# BlnTest.net
KiCad netlist of a schematic drawn in Altium Designer
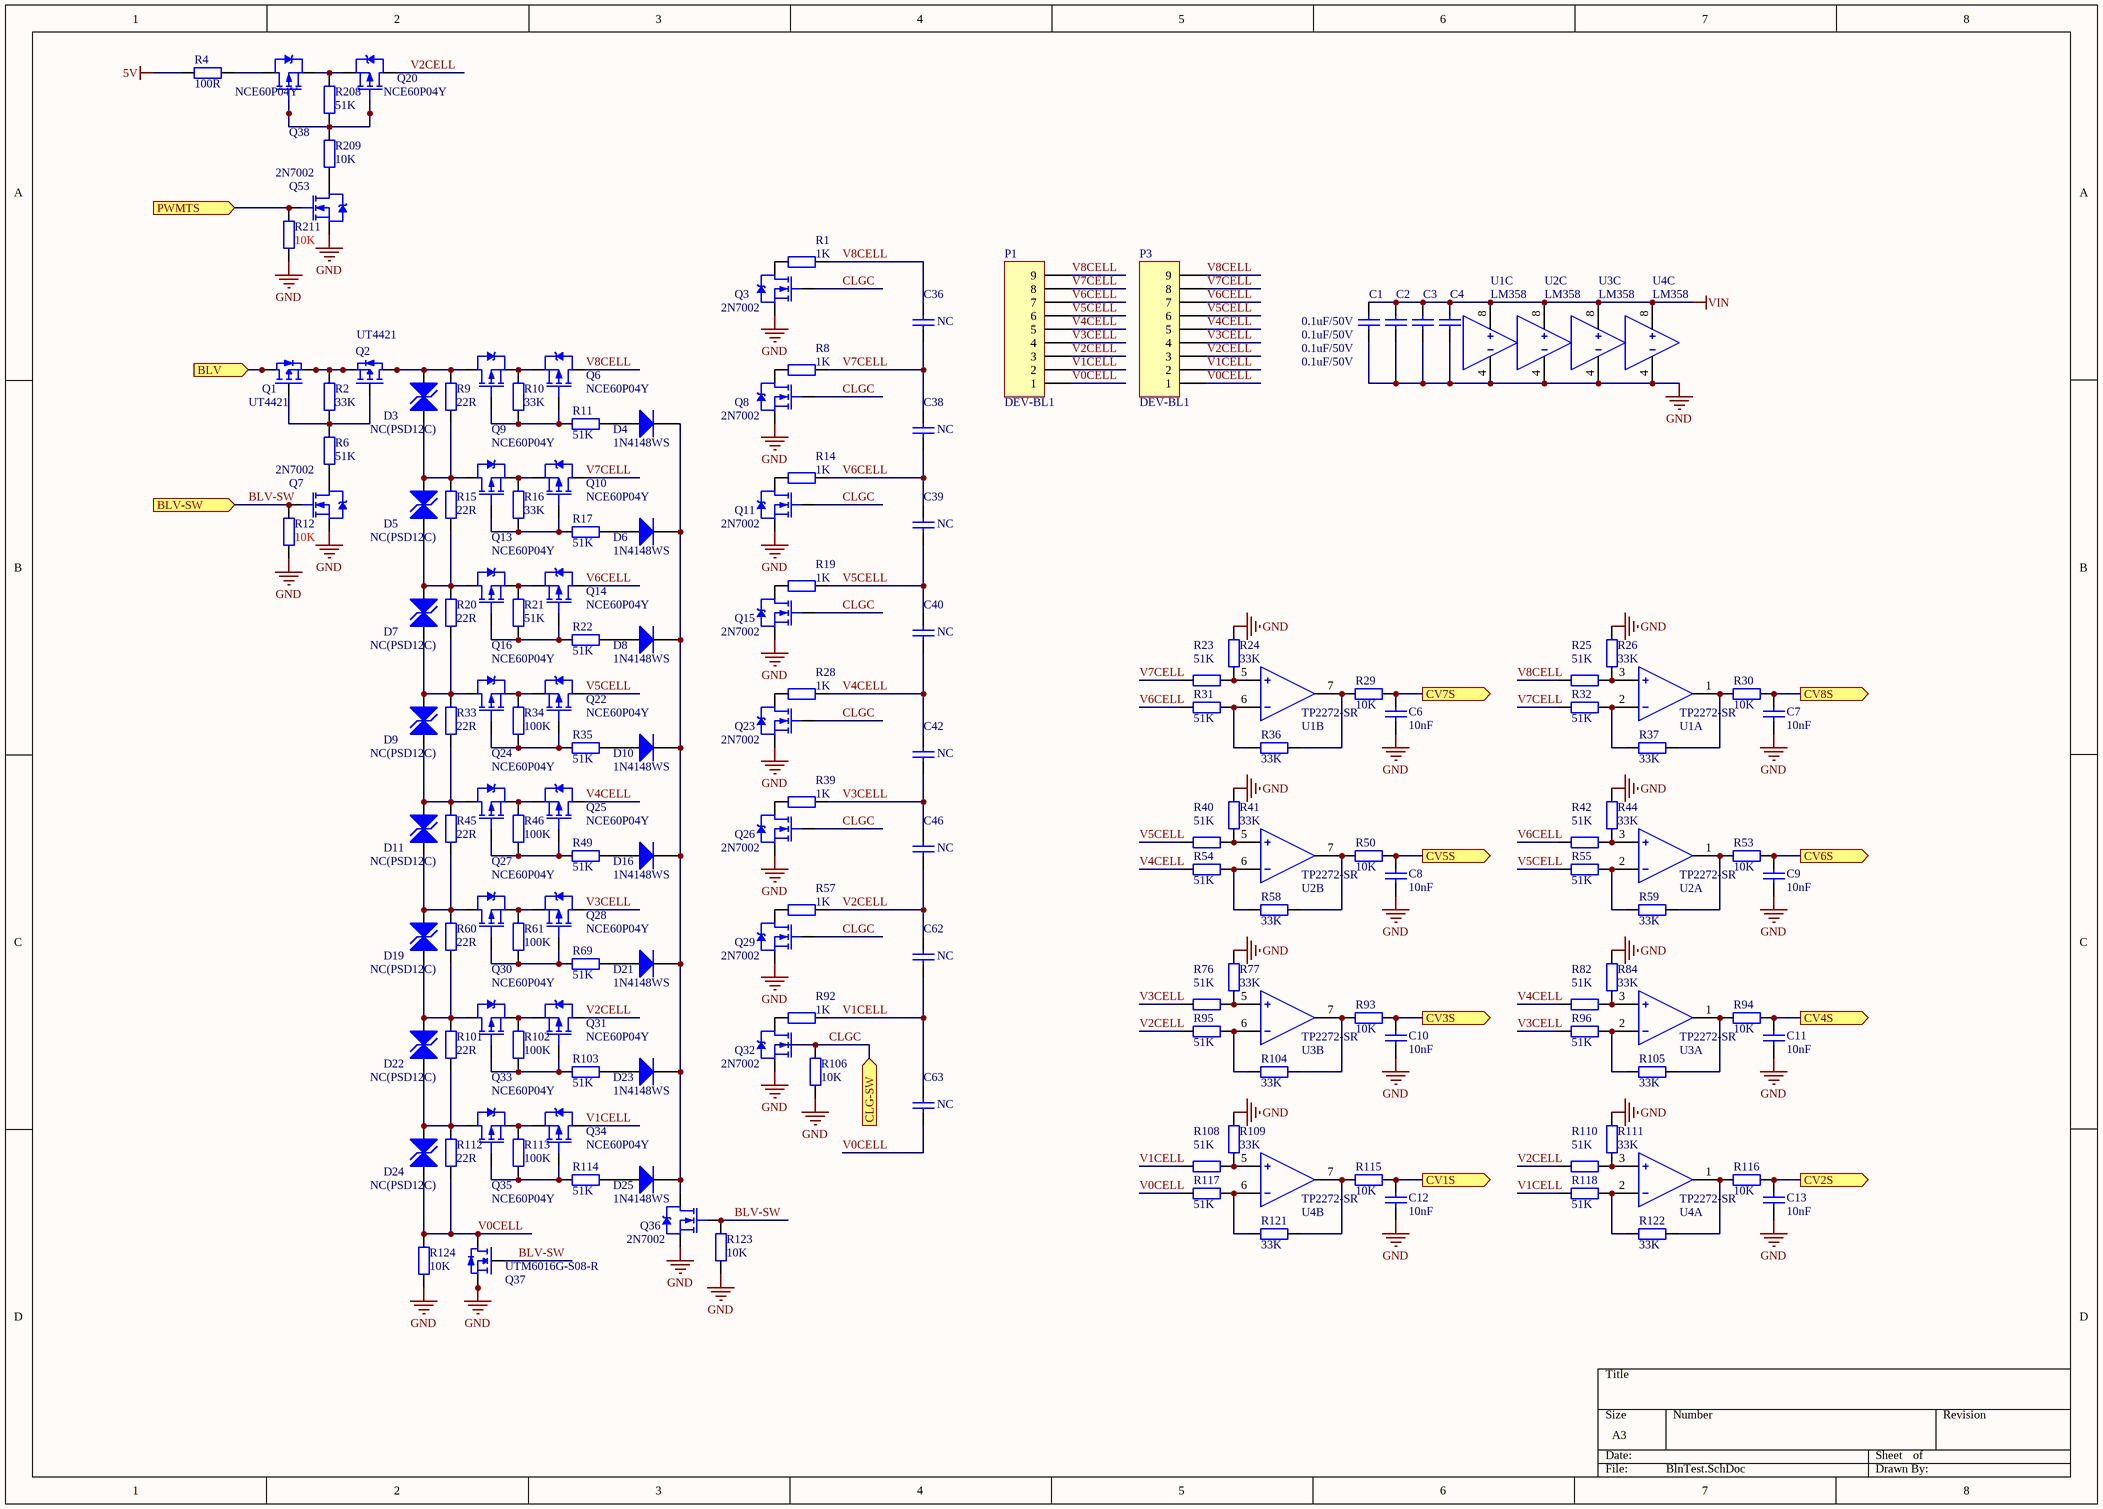
[diagram p0: BlnTest.SchDoc]

(export (version "E")
  (design (tool "Eeschema 10.0.6"))
  (components
    (comp (ref "C1")
      (value "0.1uF/50V")
      (footprint "C-0603")
      (description "Capacitor")
      (fields (field (name "PUBLISHER") "Altium Limited"))
      (libsource (lib "Miscellaneous Devices") (part "Cap"))
    )
    (comp (ref "C2")
      (value "0.1uF/50V")
      (footprint "C-0603")
      (description "Capacitor")
      (fields (field (name "PUBLISHER") "Altium Limited"))
      (libsource (lib "Miscellaneous Devices") (part "Cap"))
    )
    (comp (ref "C3")
      (value "0.1uF/50V")
      (footprint "C-0603")
      (description "Capacitor")
      (fields (field (name "PUBLISHER") "Altium Limited"))
      (libsource (lib "Miscellaneous Devices") (part "Cap"))
    )
    (comp (ref "C4")
      (value "0.1uF/50V")
      (footprint "C-0603")
      (description "Capacitor")
      (fields (field (name "PUBLISHER") "Altium Limited"))
      (libsource (lib "Miscellaneous Devices") (part "Cap"))
    )
    (comp (ref "C6")
      (value "10nF")
      (footprint "C-0603")
      (description "Capacitor")
      (fields (field (name "PUBLISHER") "Altium Limited"))
      (libsource (lib "Miscellaneous Devices") (part "Cap"))
    )
    (comp (ref "C7")
      (value "10nF")
      (footprint "C-0603")
      (description "Capacitor")
      (fields (field (name "PUBLISHER") "Altium Limited"))
      (libsource (lib "Miscellaneous Devices") (part "Cap"))
    )
    (comp (ref "C8")
      (value "10nF")
      (footprint "C-0603")
      (description "Capacitor")
      (fields (field (name "PUBLISHER") "Altium Limited"))
      (libsource (lib "Miscellaneous Devices") (part "Cap"))
    )
    (comp (ref "C9")
      (value "10nF")
      (footprint "C-0603")
      (description "Capacitor")
      (fields (field (name "PUBLISHER") "Altium Limited"))
      (libsource (lib "Miscellaneous Devices") (part "Cap"))
    )
    (comp (ref "C10")
      (value "10nF")
      (footprint "C-0603")
      (description "Capacitor")
      (fields (field (name "PUBLISHER") "Altium Limited"))
      (libsource (lib "Miscellaneous Devices") (part "Cap"))
    )
    (comp (ref "C11")
      (value "10nF")
      (footprint "C-0603")
      (description "Capacitor")
      (fields (field (name "PUBLISHER") "Altium Limited"))
      (libsource (lib "Miscellaneous Devices") (part "Cap"))
    )
    (comp (ref "C12")
      (value "10nF")
      (footprint "C-0603")
      (description "Capacitor")
      (fields (field (name "PUBLISHER") "Altium Limited"))
      (libsource (lib "Miscellaneous Devices") (part "Cap"))
    )
    (comp (ref "C13")
      (value "10nF")
      (footprint "C-0603")
      (description "Capacitor")
      (fields (field (name "PUBLISHER") "Altium Limited"))
      (libsource (lib "Miscellaneous Devices") (part "Cap"))
    )
    (comp (ref "C36")
      (value "NC")
      (footprint "C-0805")
      (description "Capacitor")
      (fields (field (name "PUBLISHER") "Altium Limited"))
      (libsource (lib "Miscellaneous Devices") (part "Cap"))
    )
    (comp (ref "C38")
      (value "NC")
      (footprint "C-0805")
      (description "Capacitor")
      (fields (field (name "PUBLISHER") "Altium Limited"))
      (libsource (lib "Miscellaneous Devices") (part "Cap"))
    )
    (comp (ref "C39")
      (value "NC")
      (footprint "C-0805")
      (description "Capacitor")
      (fields (field (name "PUBLISHER") "Altium Limited"))
      (libsource (lib "Miscellaneous Devices") (part "Cap"))
    )
    (comp (ref "C40")
      (value "NC")
      (footprint "C-0805")
      (description "Capacitor")
      (fields (field (name "PUBLISHER") "Altium Limited"))
      (libsource (lib "Miscellaneous Devices") (part "Cap"))
    )
    (comp (ref "C42")
      (value "NC")
      (footprint "C-0805")
      (description "Capacitor")
      (fields (field (name "PUBLISHER") "Altium Limited"))
      (libsource (lib "Miscellaneous Devices") (part "Cap"))
    )
    (comp (ref "C46")
      (value "NC")
      (footprint "C-0805")
      (description "Capacitor")
      (fields (field (name "PUBLISHER") "Altium Limited"))
      (libsource (lib "Miscellaneous Devices") (part "Cap"))
    )
    (comp (ref "C62")
      (value "NC")
      (footprint "C-0805")
      (description "Capacitor")
      (fields (field (name "PUBLISHER") "Altium Limited"))
      (libsource (lib "Miscellaneous Devices") (part "Cap"))
    )
    (comp (ref "C63")
      (value "NC")
      (footprint "C-0805")
      (description "Capacitor")
      (fields (field (name "PUBLISHER") "Altium Limited"))
      (libsource (lib "Miscellaneous Devices") (part "Cap"))
    )
    (comp (ref "D3") (value "NC(PSD12C)") (footprint "SOD-323") (libsource (lib "ToboxStd") (part "TVS-D")))
    (comp (ref "D4")
      (value "1N4148WS")
      (footprint "SOD-323")
      (description "Default Diode")
      (fields (field (name "PUBLISHER") "Altium Limited"))
      (libsource (lib "Miscellaneous Devices") (part "Diode"))
    )
    (comp (ref "D5") (value "NC(PSD12C)") (footprint "SOD-323") (libsource (lib "ToboxStd") (part "TVS-D")))
    (comp (ref "D6")
      (value "1N4148WS")
      (footprint "SOD-323")
      (description "Default Diode")
      (fields (field (name "PUBLISHER") "Altium Limited"))
      (libsource (lib "Miscellaneous Devices") (part "Diode"))
    )
    (comp (ref "D7") (value "NC(PSD12C)") (footprint "SOD-323") (libsource (lib "ToboxStd") (part "TVS-D")))
    (comp (ref "D8")
      (value "1N4148WS")
      (footprint "SOD-323")
      (description "Default Diode")
      (fields (field (name "PUBLISHER") "Altium Limited"))
      (libsource (lib "Miscellaneous Devices") (part "Diode"))
    )
    (comp (ref "D9") (value "NC(PSD12C)") (footprint "SOD-323") (libsource (lib "ToboxStd") (part "TVS-D")))
    (comp (ref "D10")
      (value "1N4148WS")
      (footprint "SOD-323")
      (description "Default Diode")
      (fields (field (name "PUBLISHER") "Altium Limited"))
      (libsource (lib "Miscellaneous Devices") (part "Diode"))
    )
    (comp (ref "D11") (value "NC(PSD12C)") (footprint "SOD-323") (libsource (lib "ToboxStd") (part "TVS-D")))
    (comp (ref "D16")
      (value "1N4148WS")
      (footprint "SOD-323")
      (description "Default Diode")
      (fields (field (name "PUBLISHER") "Altium Limited"))
      (libsource (lib "Miscellaneous Devices") (part "Diode"))
    )
    (comp (ref "D19") (value "NC(PSD12C)") (footprint "SOD-323") (libsource (lib "ToboxStd") (part "TVS-D")))
    (comp (ref "D21")
      (value "1N4148WS")
      (footprint "SOD-323")
      (description "Default Diode")
      (fields (field (name "PUBLISHER") "Altium Limited"))
      (libsource (lib "Miscellaneous Devices") (part "Diode"))
    )
    (comp (ref "D22") (value "NC(PSD12C)") (footprint "SOD-323") (libsource (lib "ToboxStd") (part "TVS-D")))
    (comp (ref "D23")
      (value "1N4148WS")
      (footprint "SOD-323")
      (description "Default Diode")
      (fields (field (name "PUBLISHER") "Altium Limited"))
      (libsource (lib "Miscellaneous Devices") (part "Diode"))
    )
    (comp (ref "D24") (value "NC(PSD12C)") (footprint "SOD-323") (libsource (lib "ToboxStd") (part "TVS-D")))
    (comp (ref "D25")
      (value "1N4148WS")
      (footprint "SOD-323")
      (description "Default Diode")
      (fields (field (name "PUBLISHER") "Altium Limited"))
      (libsource (lib "Miscellaneous Devices") (part "Diode"))
    )
    (comp (ref "P1")
      (value "DEV-BL1")
      (footprint "XH 2.54-9P")
      (description "Header, 9-Pin")
      (fields (field (name "PUBLISHER") "Altium Limited"))
      (libsource (lib "Miscellaneous Connectors") (part "Header 9"))
    )
    (comp (ref "P3")
      (value "DEV-BL1")
      (footprint "XH 2.54-9P")
      (description "Header, 9-Pin")
      (fields (field (name "PUBLISHER") "Altium Limited"))
      (libsource (lib "Miscellaneous Connectors") (part "Header 9"))
    )
    (comp (ref "Q1")
      (value "UT4421")
      (footprint "SOIC8")
      (description "SO8-PMOS")
      (libsource (lib "Tobox") (part "SO8-PMOS"))
    )
    (comp (ref "Q2")
      (value "UT4421")
      (footprint "SOIC8")
      (description "SO8-PMOS")
      (libsource (lib "Tobox") (part "SO8-PMOS"))
    )
    (comp (ref "Q3")
      (value "2N7002")
      (footprint "SOT23-3")
      (description "N-Channel Power MOSFET")
      (fields (field (name "PUBLISHER") "Altium Limited"))
      (libsource (lib "Miscellaneous Devices") (part "NMOS-2"))
    )
    (comp (ref "Q6")
      (value "NCE60P04Y")
      (footprint "SOT23-3")
      (description "P-Channel Power MOSFET")
      (fields (field (name "PUBLISHER") "Altium Limited"))
      (libsource (lib "Miscellaneous Devices") (part "PMOS-2"))
    )
    (comp (ref "Q7")
      (value "2N7002")
      (footprint "SOT23-3")
      (description "N-Channel Power MOSFET")
      (fields (field (name "PUBLISHER") "Altium Limited"))
      (libsource (lib "Miscellaneous Devices") (part "NMOS-2"))
    )
    (comp (ref "Q8")
      (value "2N7002")
      (footprint "SOT23-3")
      (description "N-Channel Power MOSFET")
      (fields (field (name "PUBLISHER") "Altium Limited"))
      (libsource (lib "Miscellaneous Devices") (part "NMOS-2"))
    )
    (comp (ref "Q9")
      (value "NCE60P04Y")
      (footprint "SOT23-3")
      (description "P-Channel Power MOSFET")
      (fields (field (name "PUBLISHER") "Altium Limited"))
      (libsource (lib "Miscellaneous Devices") (part "PMOS-2"))
    )
    (comp (ref "Q10")
      (value "NCE60P04Y")
      (footprint "SOT23-3")
      (description "P-Channel Power MOSFET")
      (fields (field (name "PUBLISHER") "Altium Limited"))
      (libsource (lib "Miscellaneous Devices") (part "PMOS-2"))
    )
    (comp (ref "Q11")
      (value "2N7002")
      (footprint "SOT23-3")
      (description "N-Channel Power MOSFET")
      (fields (field (name "PUBLISHER") "Altium Limited"))
      (libsource (lib "Miscellaneous Devices") (part "NMOS-2"))
    )
    (comp (ref "Q13")
      (value "NCE60P04Y")
      (footprint "SOT23-3")
      (description "P-Channel Power MOSFET")
      (fields (field (name "PUBLISHER") "Altium Limited"))
      (libsource (lib "Miscellaneous Devices") (part "PMOS-2"))
    )
    (comp (ref "Q14")
      (value "NCE60P04Y")
      (footprint "SOT23-3")
      (description "P-Channel Power MOSFET")
      (fields (field (name "PUBLISHER") "Altium Limited"))
      (libsource (lib "Miscellaneous Devices") (part "PMOS-2"))
    )
    (comp (ref "Q15")
      (value "2N7002")
      (footprint "SOT23-3")
      (description "N-Channel Power MOSFET")
      (fields (field (name "PUBLISHER") "Altium Limited"))
      (libsource (lib "Miscellaneous Devices") (part "NMOS-2"))
    )
    (comp (ref "Q16")
      (value "NCE60P04Y")
      (footprint "SOT23-3")
      (description "P-Channel Power MOSFET")
      (fields (field (name "PUBLISHER") "Altium Limited"))
      (libsource (lib "Miscellaneous Devices") (part "PMOS-2"))
    )
    (comp (ref "Q20")
      (value "NCE60P04Y")
      (footprint "SOT23-3")
      (description "P-Channel Power MOSFET")
      (fields (field (name "PUBLISHER") "Altium Limited"))
      (libsource (lib "Miscellaneous Devices") (part "PMOS-2"))
    )
    (comp (ref "Q22")
      (value "NCE60P04Y")
      (footprint "SOT23-3")
      (description "P-Channel Power MOSFET")
      (fields (field (name "PUBLISHER") "Altium Limited"))
      (libsource (lib "Miscellaneous Devices") (part "PMOS-2"))
    )
    (comp (ref "Q23")
      (value "2N7002")
      (footprint "SOT23-3")
      (description "N-Channel Power MOSFET")
      (fields (field (name "PUBLISHER") "Altium Limited"))
      (libsource (lib "Miscellaneous Devices") (part "NMOS-2"))
    )
    (comp (ref "Q24")
      (value "NCE60P04Y")
      (footprint "SOT23-3")
      (description "P-Channel Power MOSFET")
      (fields (field (name "PUBLISHER") "Altium Limited"))
      (libsource (lib "Miscellaneous Devices") (part "PMOS-2"))
    )
    (comp (ref "Q25")
      (value "NCE60P04Y")
      (footprint "SOT23-3")
      (description "P-Channel Power MOSFET")
      (fields (field (name "PUBLISHER") "Altium Limited"))
      (libsource (lib "Miscellaneous Devices") (part "PMOS-2"))
    )
    (comp (ref "Q26")
      (value "2N7002")
      (footprint "SOT23-3")
      (description "N-Channel Power MOSFET")
      (fields (field (name "PUBLISHER") "Altium Limited"))
      (libsource (lib "Miscellaneous Devices") (part "NMOS-2"))
    )
    (comp (ref "Q27")
      (value "NCE60P04Y")
      (footprint "SOT23-3")
      (description "P-Channel Power MOSFET")
      (fields (field (name "PUBLISHER") "Altium Limited"))
      (libsource (lib "Miscellaneous Devices") (part "PMOS-2"))
    )
    (comp (ref "Q28")
      (value "NCE60P04Y")
      (footprint "SOT23-3")
      (description "P-Channel Power MOSFET")
      (fields (field (name "PUBLISHER") "Altium Limited"))
      (libsource (lib "Miscellaneous Devices") (part "PMOS-2"))
    )
    (comp (ref "Q29")
      (value "2N7002")
      (footprint "SOT23-3")
      (description "N-Channel Power MOSFET")
      (fields (field (name "PUBLISHER") "Altium Limited"))
      (libsource (lib "Miscellaneous Devices") (part "NMOS-2"))
    )
    (comp (ref "Q30")
      (value "NCE60P04Y")
      (footprint "SOT23-3")
      (description "P-Channel Power MOSFET")
      (fields (field (name "PUBLISHER") "Altium Limited"))
      (libsource (lib "Miscellaneous Devices") (part "PMOS-2"))
    )
    (comp (ref "Q31")
      (value "NCE60P04Y")
      (footprint "SOT23-3")
      (description "P-Channel Power MOSFET")
      (fields (field (name "PUBLISHER") "Altium Limited"))
      (libsource (lib "Miscellaneous Devices") (part "PMOS-2"))
    )
    (comp (ref "Q32")
      (value "2N7002")
      (footprint "SOT23-3")
      (description "N-Channel Power MOSFET")
      (fields (field (name "PUBLISHER") "Altium Limited"))
      (libsource (lib "Miscellaneous Devices") (part "NMOS-2"))
    )
    (comp (ref "Q33")
      (value "NCE60P04Y")
      (footprint "SOT23-3")
      (description "P-Channel Power MOSFET")
      (fields (field (name "PUBLISHER") "Altium Limited"))
      (libsource (lib "Miscellaneous Devices") (part "PMOS-2"))
    )
    (comp (ref "Q34")
      (value "NCE60P04Y")
      (footprint "SOT23-3")
      (description "P-Channel Power MOSFET")
      (fields (field (name "PUBLISHER") "Altium Limited"))
      (libsource (lib "Miscellaneous Devices") (part "PMOS-2"))
    )
    (comp (ref "Q35")
      (value "NCE60P04Y")
      (footprint "SOT23-3")
      (description "P-Channel Power MOSFET")
      (fields (field (name "PUBLISHER") "Altium Limited"))
      (libsource (lib "Miscellaneous Devices") (part "PMOS-2"))
    )
    (comp (ref "Q36")
      (value "2N7002")
      (footprint "SOT23-3")
      (description "N-Channel Power MOSFET")
      (fields (field (name "PUBLISHER") "Altium Limited"))
      (libsource (lib "Miscellaneous Devices") (part "NMOS-2"))
    )
    (comp (ref "Q37")
      (value "UTM6016G-S08-R")
      (footprint "SOIC8")
      (description "SO8-NMOS")
      (libsource (lib "Tobox") (part "SO8-NMOS"))
    )
    (comp (ref "Q38")
      (value "NCE60P04Y")
      (footprint "SOT23-3")
      (description "P-Channel Power MOSFET")
      (fields (field (name "PUBLISHER") "Altium Limited"))
      (libsource (lib "Miscellaneous Devices") (part "PMOS-2"))
    )
    (comp (ref "Q53")
      (value "2N7002")
      (footprint "SOT23-3")
      (description "N-Channel Power MOSFET")
      (fields (field (name "PUBLISHER") "Altium Limited"))
      (libsource (lib "Miscellaneous Devices") (part "NMOS-2"))
    )
    (comp (ref "R1")
      (value "1K")
      (footprint "R-0603")
      (description "Resistor")
      (fields (field (name "PUBLISHER") "Altium Limited"))
      (libsource (lib "") (part "Res2_2"))
    )
    (comp (ref "R2")
      (value "33K")
      (footprint "R-0603")
      (description "Resistor")
      (fields (field (name "PUBLISHER") "Altium Limited"))
      (libsource (lib "") (part "Res2_2"))
    )
    (comp (ref "R4")
      (value "100R")
      (footprint "R-0603")
      (description "Resistor")
      (fields (field (name "PUBLISHER") "Altium Limited"))
      (libsource (lib "") (part "Res2_3"))
    )
    (comp (ref "R6")
      (value "51K")
      (footprint "R-0603")
      (description "Resistor")
      (fields (field (name "PUBLISHER") "Altium Limited"))
      (libsource (lib "") (part "Res2_2"))
    )
    (comp (ref "R8")
      (value "1K")
      (footprint "R-0603")
      (description "Resistor")
      (fields (field (name "PUBLISHER") "Altium Limited"))
      (libsource (lib "") (part "Res2_2"))
    )
    (comp (ref "R9")
      (value "22R")
      (footprint "RES 3W-S")
      (description "Resistor")
      (fields (field (name "PUBLISHER") "Altium Limited"))
      (libsource (lib "") (part "Res2_1"))
    )
    (comp (ref "R10")
      (value "33K")
      (footprint "R-0603")
      (description "Resistor")
      (fields (field (name "PUBLISHER") "Altium Limited"))
      (libsource (lib "") (part "Res2_3"))
    )
    (comp (ref "R11")
      (value "51K")
      (footprint "R-0603")
      (description "Resistor")
      (fields (field (name "PUBLISHER") "Altium Limited"))
      (libsource (lib "Miscellaneous Devices") (part "Res2"))
    )
    (comp (ref "R12")
      (value "10K")
      (footprint "R-0603")
      (description "Resistor")
      (fields (field (name "PUBLISHER") "Altium Limited"))
      (libsource (lib "") (part "Res2_3"))
    )
    (comp (ref "R14")
      (value "1K")
      (footprint "R-0603")
      (description "Resistor")
      (fields (field (name "PUBLISHER") "Altium Limited"))
      (libsource (lib "") (part "Res2_2"))
    )
    (comp (ref "R15")
      (value "22R")
      (footprint "RES 3W-S")
      (description "Resistor")
      (fields (field (name "PUBLISHER") "Altium Limited"))
      (libsource (lib "") (part "Res2_1"))
    )
    (comp (ref "R16")
      (value "33K")
      (footprint "R-0603")
      (description "Resistor")
      (fields (field (name "PUBLISHER") "Altium Limited"))
      (libsource (lib "") (part "Res2_3"))
    )
    (comp (ref "R17")
      (value "51K")
      (footprint "R-0603")
      (description "Resistor")
      (fields (field (name "PUBLISHER") "Altium Limited"))
      (libsource (lib "Miscellaneous Devices") (part "Res2"))
    )
    (comp (ref "R19")
      (value "1K")
      (footprint "R-0603")
      (description "Resistor")
      (fields (field (name "PUBLISHER") "Altium Limited"))
      (libsource (lib "") (part "Res2_2"))
    )
    (comp (ref "R20")
      (value "22R")
      (footprint "RES 3W-S")
      (description "Resistor")
      (fields (field (name "PUBLISHER") "Altium Limited"))
      (libsource (lib "") (part "Res2_1"))
    )
    (comp (ref "R21")
      (value "51K")
      (footprint "R-0603")
      (description "Resistor")
      (fields (field (name "PUBLISHER") "Altium Limited"))
      (libsource (lib "") (part "Res2_3"))
    )
    (comp (ref "R22")
      (value "51K")
      (footprint "R-0603")
      (description "Resistor")
      (fields (field (name "PUBLISHER") "Altium Limited"))
      (libsource (lib "Miscellaneous Devices") (part "Res2"))
    )
    (comp (ref "R23")
      (value "51K")
      (footprint "R-0603")
      (description "Resistor")
      (fields (field (name "PUBLISHER") "Altium Limited"))
      (libsource (lib "Miscellaneous Devices") (part "Res2"))
    )
    (comp (ref "R24")
      (value "33K")
      (footprint "R-0603")
      (description "Resistor")
      (fields (field (name "PUBLISHER") "Altium Limited"))
      (libsource (lib "") (part "Res2_3"))
    )
    (comp (ref "R25")
      (value "51K")
      (footprint "R-0603")
      (description "Resistor")
      (fields (field (name "PUBLISHER") "Altium Limited"))
      (libsource (lib "Miscellaneous Devices") (part "Res2"))
    )
    (comp (ref "R26")
      (value "33K")
      (footprint "R-0603")
      (description "Resistor")
      (fields (field (name "PUBLISHER") "Altium Limited"))
      (libsource (lib "") (part "Res2_3"))
    )
    (comp (ref "R28")
      (value "1K")
      (footprint "R-0603")
      (description "Resistor")
      (fields (field (name "PUBLISHER") "Altium Limited"))
      (libsource (lib "") (part "Res2_2"))
    )
    (comp (ref "R29")
      (value "10K")
      (footprint "R-0603")
      (description "Resistor")
      (fields (field (name "PUBLISHER") "Altium Limited"))
      (libsource (lib "Miscellaneous Devices") (part "Res2"))
    )
    (comp (ref "R30")
      (value "10K")
      (footprint "R-0603")
      (description "Resistor")
      (fields (field (name "PUBLISHER") "Altium Limited"))
      (libsource (lib "Miscellaneous Devices") (part "Res2"))
    )
    (comp (ref "R31")
      (value "51K")
      (footprint "R-0603")
      (description "Resistor")
      (fields (field (name "PUBLISHER") "Altium Limited"))
      (libsource (lib "") (part "Res2_2"))
    )
    (comp (ref "R32")
      (value "51K")
      (footprint "R-0603")
      (description "Resistor")
      (fields (field (name "PUBLISHER") "Altium Limited"))
      (libsource (lib "") (part "Res2_2"))
    )
    (comp (ref "R33")
      (value "22R")
      (footprint "RES 3W-S")
      (description "Resistor")
      (fields (field (name "PUBLISHER") "Altium Limited"))
      (libsource (lib "") (part "Res2_1"))
    )
    (comp (ref "R34")
      (value "100K")
      (footprint "R-0603")
      (description "Resistor")
      (fields (field (name "PUBLISHER") "Altium Limited"))
      (libsource (lib "") (part "Res2_3"))
    )
    (comp (ref "R35")
      (value "51K")
      (footprint "R-0603")
      (description "Resistor")
      (fields (field (name "PUBLISHER") "Altium Limited"))
      (libsource (lib "Miscellaneous Devices") (part "Res2"))
    )
    (comp (ref "R36")
      (value "33K")
      (footprint "R-0603")
      (description "Resistor")
      (fields (field (name "PUBLISHER") "Altium Limited"))
      (libsource (lib "") (part "Res2_2"))
    )
    (comp (ref "R37")
      (value "33K")
      (footprint "R-0603")
      (description "Resistor")
      (fields (field (name "PUBLISHER") "Altium Limited"))
      (libsource (lib "") (part "Res2_2"))
    )
    (comp (ref "R39")
      (value "1K")
      (footprint "R-0603")
      (description "Resistor")
      (fields (field (name "PUBLISHER") "Altium Limited"))
      (libsource (lib "") (part "Res2_2"))
    )
    (comp (ref "R40")
      (value "51K")
      (footprint "R-0603")
      (description "Resistor")
      (fields (field (name "PUBLISHER") "Altium Limited"))
      (libsource (lib "Miscellaneous Devices") (part "Res2"))
    )
    (comp (ref "R41")
      (value "33K")
      (footprint "R-0603")
      (description "Resistor")
      (fields (field (name "PUBLISHER") "Altium Limited"))
      (libsource (lib "") (part "Res2_3"))
    )
    (comp (ref "R42")
      (value "51K")
      (footprint "R-0603")
      (description "Resistor")
      (fields (field (name "PUBLISHER") "Altium Limited"))
      (libsource (lib "Miscellaneous Devices") (part "Res2"))
    )
    (comp (ref "R44")
      (value "33K")
      (footprint "R-0603")
      (description "Resistor")
      (fields (field (name "PUBLISHER") "Altium Limited"))
      (libsource (lib "") (part "Res2_3"))
    )
    (comp (ref "R45")
      (value "22R")
      (footprint "RES 3W-S")
      (description "Resistor")
      (fields (field (name "PUBLISHER") "Altium Limited"))
      (libsource (lib "") (part "Res2_1"))
    )
    (comp (ref "R46")
      (value "100K")
      (footprint "R-0603")
      (description "Resistor")
      (fields (field (name "PUBLISHER") "Altium Limited"))
      (libsource (lib "") (part "Res2_3"))
    )
    (comp (ref "R49")
      (value "51K")
      (footprint "R-0603")
      (description "Resistor")
      (fields (field (name "PUBLISHER") "Altium Limited"))
      (libsource (lib "Miscellaneous Devices") (part "Res2"))
    )
    (comp (ref "R50")
      (value "10K")
      (footprint "R-0603")
      (description "Resistor")
      (fields (field (name "PUBLISHER") "Altium Limited"))
      (libsource (lib "Miscellaneous Devices") (part "Res2"))
    )
    (comp (ref "R53")
      (value "10K")
      (footprint "R-0603")
      (description "Resistor")
      (fields (field (name "PUBLISHER") "Altium Limited"))
      (libsource (lib "Miscellaneous Devices") (part "Res2"))
    )
    (comp (ref "R54")
      (value "51K")
      (footprint "R-0603")
      (description "Resistor")
      (fields (field (name "PUBLISHER") "Altium Limited"))
      (libsource (lib "") (part "Res2_2"))
    )
    (comp (ref "R55")
      (value "51K")
      (footprint "R-0603")
      (description "Resistor")
      (fields (field (name "PUBLISHER") "Altium Limited"))
      (libsource (lib "") (part "Res2_2"))
    )
    (comp (ref "R57")
      (value "1K")
      (footprint "R-0603")
      (description "Resistor")
      (fields (field (name "PUBLISHER") "Altium Limited"))
      (libsource (lib "") (part "Res2_2"))
    )
    (comp (ref "R58")
      (value "33K")
      (footprint "R-0603")
      (description "Resistor")
      (fields (field (name "PUBLISHER") "Altium Limited"))
      (libsource (lib "") (part "Res2_2"))
    )
    (comp (ref "R59")
      (value "33K")
      (footprint "R-0603")
      (description "Resistor")
      (fields (field (name "PUBLISHER") "Altium Limited"))
      (libsource (lib "") (part "Res2_2"))
    )
    (comp (ref "R60")
      (value "22R")
      (footprint "RES 3W-S")
      (description "Resistor")
      (fields (field (name "PUBLISHER") "Altium Limited"))
      (libsource (lib "") (part "Res2_1"))
    )
    (comp (ref "R61")
      (value "100K")
      (footprint "R-0603")
      (description "Resistor")
      (fields (field (name "PUBLISHER") "Altium Limited"))
      (libsource (lib "") (part "Res2_3"))
    )
    (comp (ref "R69")
      (value "51K")
      (footprint "R-0603")
      (description "Resistor")
      (fields (field (name "PUBLISHER") "Altium Limited"))
      (libsource (lib "Miscellaneous Devices") (part "Res2"))
    )
    (comp (ref "R76")
      (value "51K")
      (footprint "R-0603")
      (description "Resistor")
      (fields (field (name "PUBLISHER") "Altium Limited"))
      (libsource (lib "Miscellaneous Devices") (part "Res2"))
    )
    (comp (ref "R77")
      (value "33K")
      (footprint "R-0603")
      (description "Resistor")
      (fields (field (name "PUBLISHER") "Altium Limited"))
      (libsource (lib "") (part "Res2_3"))
    )
    (comp (ref "R82")
      (value "51K")
      (footprint "R-0603")
      (description "Resistor")
      (fields (field (name "PUBLISHER") "Altium Limited"))
      (libsource (lib "Miscellaneous Devices") (part "Res2"))
    )
    (comp (ref "R84")
      (value "33K")
      (footprint "R-0603")
      (description "Resistor")
      (fields (field (name "PUBLISHER") "Altium Limited"))
      (libsource (lib "") (part "Res2_3"))
    )
    (comp (ref "R92")
      (value "1K")
      (footprint "R-0603")
      (description "Resistor")
      (fields (field (name "PUBLISHER") "Altium Limited"))
      (libsource (lib "") (part "Res2_2"))
    )
    (comp (ref "R93")
      (value "10K")
      (footprint "R-0603")
      (description "Resistor")
      (fields (field (name "PUBLISHER") "Altium Limited"))
      (libsource (lib "Miscellaneous Devices") (part "Res2"))
    )
    (comp (ref "R94")
      (value "10K")
      (footprint "R-0603")
      (description "Resistor")
      (fields (field (name "PUBLISHER") "Altium Limited"))
      (libsource (lib "Miscellaneous Devices") (part "Res2"))
    )
    (comp (ref "R95")
      (value "51K")
      (footprint "R-0603")
      (description "Resistor")
      (fields (field (name "PUBLISHER") "Altium Limited"))
      (libsource (lib "") (part "Res2_2"))
    )
    (comp (ref "R96")
      (value "51K")
      (footprint "R-0603")
      (description "Resistor")
      (fields (field (name "PUBLISHER") "Altium Limited"))
      (libsource (lib "") (part "Res2_2"))
    )
    (comp (ref "R101")
      (value "22R")
      (footprint "RES 3W-S")
      (description "Resistor")
      (fields (field (name "PUBLISHER") "Altium Limited"))
      (libsource (lib "") (part "Res2_1"))
    )
    (comp (ref "R102")
      (value "100K")
      (footprint "R-0603")
      (description "Resistor")
      (fields (field (name "PUBLISHER") "Altium Limited"))
      (libsource (lib "") (part "Res2_3"))
    )
    (comp (ref "R103")
      (value "51K")
      (footprint "R-0603")
      (description "Resistor")
      (fields (field (name "PUBLISHER") "Altium Limited"))
      (libsource (lib "Miscellaneous Devices") (part "Res2"))
    )
    (comp (ref "R104")
      (value "33K")
      (footprint "R-0603")
      (description "Resistor")
      (fields (field (name "PUBLISHER") "Altium Limited"))
      (libsource (lib "") (part "Res2_2"))
    )
    (comp (ref "R105")
      (value "33K")
      (footprint "R-0603")
      (description "Resistor")
      (fields (field (name "PUBLISHER") "Altium Limited"))
      (libsource (lib "") (part "Res2_2"))
    )
    (comp (ref "R106")
      (value "10K")
      (footprint "R-0603")
      (description "Resistor")
      (fields (field (name "PUBLISHER") "Altium Limited"))
      (libsource (lib "") (part "Res2_1"))
    )
    (comp (ref "R108")
      (value "51K")
      (footprint "R-0603")
      (description "Resistor")
      (fields (field (name "PUBLISHER") "Altium Limited"))
      (libsource (lib "Miscellaneous Devices") (part "Res2"))
    )
    (comp (ref "R109")
      (value "33K")
      (footprint "R-0603")
      (description "Resistor")
      (fields (field (name "PUBLISHER") "Altium Limited"))
      (libsource (lib "") (part "Res2_3"))
    )
    (comp (ref "R110")
      (value "51K")
      (footprint "R-0603")
      (description "Resistor")
      (fields (field (name "PUBLISHER") "Altium Limited"))
      (libsource (lib "Miscellaneous Devices") (part "Res2"))
    )
    (comp (ref "R111")
      (value "33K")
      (footprint "R-0603")
      (description "Resistor")
      (fields (field (name "PUBLISHER") "Altium Limited"))
      (libsource (lib "") (part "Res2_3"))
    )
    (comp (ref "R112")
      (value "22R")
      (footprint "RES 3W-S")
      (description "Resistor")
      (fields (field (name "PUBLISHER") "Altium Limited"))
      (libsource (lib "") (part "Res2_1"))
    )
    (comp (ref "R113")
      (value "100K")
      (footprint "R-0603")
      (description "Resistor")
      (fields (field (name "PUBLISHER") "Altium Limited"))
      (libsource (lib "") (part "Res2_3"))
    )
    (comp (ref "R114")
      (value "51K")
      (footprint "R-0603")
      (description "Resistor")
      (fields (field (name "PUBLISHER") "Altium Limited"))
      (libsource (lib "Miscellaneous Devices") (part "Res2"))
    )
    (comp (ref "R115")
      (value "10K")
      (footprint "R-0603")
      (description "Resistor")
      (fields (field (name "PUBLISHER") "Altium Limited"))
      (libsource (lib "Miscellaneous Devices") (part "Res2"))
    )
    (comp (ref "R116")
      (value "10K")
      (footprint "R-0603")
      (description "Resistor")
      (fields (field (name "PUBLISHER") "Altium Limited"))
      (libsource (lib "Miscellaneous Devices") (part "Res2"))
    )
    (comp (ref "R117")
      (value "51K")
      (footprint "R-0603")
      (description "Resistor")
      (fields (field (name "PUBLISHER") "Altium Limited"))
      (libsource (lib "") (part "Res2_2"))
    )
    (comp (ref "R118")
      (value "51K")
      (footprint "R-0603")
      (description "Resistor")
      (fields (field (name "PUBLISHER") "Altium Limited"))
      (libsource (lib "") (part "Res2_2"))
    )
    (comp (ref "R121")
      (value "33K")
      (footprint "R-0603")
      (description "Resistor")
      (fields (field (name "PUBLISHER") "Altium Limited"))
      (libsource (lib "") (part "Res2_2"))
    )
    (comp (ref "R122")
      (value "33K")
      (footprint "R-0603")
      (description "Resistor")
      (fields (field (name "PUBLISHER") "Altium Limited"))
      (libsource (lib "") (part "Res2_2"))
    )
    (comp (ref "R123")
      (value "10K")
      (footprint "R-0603")
      (description "Resistor")
      (fields (field (name "PUBLISHER") "Altium Limited"))
      (libsource (lib "") (part "Res2_3"))
    )
    (comp (ref "R124")
      (value "10K")
      (footprint "R-1206")
      (description "Resistor")
      (fields (field (name "PUBLISHER") "Altium Limited"))
      (libsource (lib "") (part "Res2_1"))
    )
    (comp (ref "R208")
      (value "51K")
      (footprint "R-0603")
      (description "Resistor")
      (fields (field (name "PUBLISHER") "Altium Limited"))
      (libsource (lib "") (part "Res2_2"))
    )
    (comp (ref "R209")
      (value "10K")
      (footprint "R-0603")
      (description "Resistor")
      (fields (field (name "PUBLISHER") "Altium Limited"))
      (libsource (lib "") (part "Res2_2"))
    )
    (comp (ref "R211")
      (value "10K")
      (footprint "R-0603")
      (description "Resistor")
      (fields (field (name "PUBLISHER") "Altium Limited"))
      (libsource (lib "") (part "Res2_3"))
    )
    (comp (ref "U1") (value "TP2272-SR") (footprint "SOIC8") (libsource (lib "Tobox") (part "Dual_OPAMP")))
    (comp (ref "U2") (value "TP2272-SR") (footprint "SOIC8") (libsource (lib "Tobox") (part "Dual_OPAMP")))
    (comp (ref "U3") (value "LM358") (footprint "SOIC8") (libsource (lib "Tobox") (part "Dual_OPAMP")))
    (comp (ref "U4") (value "TP2272-SR") (footprint "SOIC8") (libsource (lib "Tobox") (part "Dual_OPAMP")))
  )
  (nets
    (net (code "1") (name "/BLV") (class "Default")
      (node (ref "Q1") (pin "5") (pinfunction "D_5") (pintype "passive"))
      (node (ref "Q1") (pin "6") (pinfunction "D_6") (pintype "passive"))
      (node (ref "Q1") (pin "7") (pinfunction "D_7") (pintype "passive"))
      (node (ref "Q1") (pin "8") (pinfunction "D_8") (pintype "passive"))
    )
    (net (code "2") (name "/BLV-SW") (class "Default")
      (node (ref "Q36") (pin "1") (pinfunction "G_1") (pintype "passive"))
      (node (ref "Q37") (pin "4") (pinfunction "G_4") (pintype "passive"))
      (node (ref "Q7") (pin "1") (pinfunction "G_1") (pintype "passive"))
      (node (ref "R12") (pin "1") (pinfunction "1_1") (pintype "passive"))
      (node (ref "R123") (pin "1") (pinfunction "1_1") (pintype "passive"))
    )
    (net (code "3") (name "/CLGC") (class "Default")
      (node (ref "Q11") (pin "1") (pinfunction "G_1") (pintype "passive"))
      (node (ref "Q15") (pin "1") (pinfunction "G_1") (pintype "passive"))
      (node (ref "Q23") (pin "1") (pinfunction "G_1") (pintype "passive"))
      (node (ref "Q26") (pin "1") (pinfunction "G_1") (pintype "passive"))
      (node (ref "Q29") (pin "1") (pinfunction "G_1") (pintype "passive"))
      (node (ref "Q3") (pin "1") (pinfunction "G_1") (pintype "passive"))
      (node (ref "Q32") (pin "1") (pinfunction "G_1") (pintype "passive"))
      (node (ref "Q8") (pin "1") (pinfunction "G_1") (pintype "passive"))
      (node (ref "R106") (pin "2") (pinfunction "2_2") (pintype "passive"))
    )
    (net (code "4") (name "/CV1S") (class "Default")
      (node (ref "C12") (pin "2") (pinfunction "2_2") (pintype "passive"))
      (node (ref "R115") (pin "1") (pinfunction "1_1") (pintype "passive"))
    )
    (net (code "5") (name "/CV2S") (class "Default")
      (node (ref "C13") (pin "2") (pinfunction "2_2") (pintype "passive"))
      (node (ref "R116") (pin "1") (pinfunction "1_1") (pintype "passive"))
    )
    (net (code "6") (name "/CV3S") (class "Default")
      (node (ref "C10") (pin "2") (pinfunction "2_2") (pintype "passive"))
      (node (ref "R93") (pin "1") (pinfunction "1_1") (pintype "passive"))
    )
    (net (code "7") (name "/CV4S") (class "Default")
      (node (ref "C11") (pin "2") (pinfunction "2_2") (pintype "passive"))
      (node (ref "R94") (pin "1") (pinfunction "1_1") (pintype "passive"))
    )
    (net (code "8") (name "/CV5S") (class "Default")
      (node (ref "C8") (pin "2") (pinfunction "2_2") (pintype "passive"))
      (node (ref "R50") (pin "1") (pinfunction "1_1") (pintype "passive"))
    )
    (net (code "9") (name "/CV6S") (class "Default")
      (node (ref "C9") (pin "2") (pinfunction "2_2") (pintype "passive"))
      (node (ref "R53") (pin "1") (pinfunction "1_1") (pintype "passive"))
    )
    (net (code "10") (name "/CV7S") (class "Default")
      (node (ref "C6") (pin "2") (pinfunction "2_2") (pintype "passive"))
      (node (ref "R29") (pin "1") (pinfunction "1_1") (pintype "passive"))
    )
    (net (code "11") (name "/CV8S") (class "Default")
      (node (ref "C7") (pin "2") (pinfunction "2_2") (pintype "passive"))
      (node (ref "R30") (pin "1") (pinfunction "1_1") (pintype "passive"))
    )
    (net (code "12") (name "/PWMTS") (class "Default")
      (node (ref "Q53") (pin "1") (pinfunction "G_1") (pintype "passive"))
      (node (ref "R211") (pin "1") (pinfunction "1_1") (pintype "passive"))
    )
    (net (code "13") (name "/V0CELL") (class "Default")
      (node (ref "C63") (pin "2") (pinfunction "2_2") (pintype "passive"))
      (node (ref "D24") (pin "2") (pinfunction "2_2") (pintype "passive"))
      (node (ref "P1") (pin "1") (pinfunction "1_1") (pintype "passive"))
      (node (ref "P3") (pin "1") (pinfunction "1_1") (pintype "passive"))
      (node (ref "Q37") (pin "5") (pinfunction "D_5") (pintype "passive"))
      (node (ref "Q37") (pin "6") (pinfunction "D_6") (pintype "passive"))
      (node (ref "Q37") (pin "7") (pinfunction "D_7") (pintype "passive"))
      (node (ref "Q37") (pin "8") (pinfunction "D_8") (pintype "passive"))
      (node (ref "R112") (pin "1") (pinfunction "1_1") (pintype "passive"))
      (node (ref "R117") (pin "1") (pinfunction "1_1") (pintype "passive"))
      (node (ref "R124") (pin "2") (pinfunction "2_2") (pintype "passive"))
    )
    (net (code "14") (name "/V1CELL") (class "Default")
      (node (ref "C62") (pin "2") (pinfunction "2_2") (pintype "passive"))
      (node (ref "C63") (pin "1") (pinfunction "1_1") (pintype "passive"))
      (node (ref "P1") (pin "2") (pinfunction "2_2") (pintype "passive"))
      (node (ref "P3") (pin "2") (pinfunction "2_2") (pintype "passive"))
      (node (ref "Q34") (pin "3") (pinfunction "D_3") (pintype "passive"))
      (node (ref "R108") (pin "2") (pinfunction "2_2") (pintype "passive"))
      (node (ref "R118") (pin "1") (pinfunction "1_1") (pintype "passive"))
      (node (ref "R92") (pin "2") (pinfunction "2_2") (pintype "passive"))
    )
    (net (code "15") (name "/V2CELL") (class "Default")
      (node (ref "C46") (pin "2") (pinfunction "2_2") (pintype "passive"))
      (node (ref "C62") (pin "1") (pinfunction "1_1") (pintype "passive"))
      (node (ref "P1") (pin "3") (pinfunction "3_3") (pintype "passive"))
      (node (ref "P3") (pin "3") (pinfunction "3_3") (pintype "passive"))
      (node (ref "Q20") (pin "3") (pinfunction "D_3") (pintype "passive"))
      (node (ref "Q31") (pin "3") (pinfunction "D_3") (pintype "passive"))
      (node (ref "R110") (pin "2") (pinfunction "2_2") (pintype "passive"))
      (node (ref "R57") (pin "2") (pinfunction "2_2") (pintype "passive"))
      (node (ref "R95") (pin "1") (pinfunction "1_1") (pintype "passive"))
    )
    (net (code "16") (name "/V3CELL") (class "Default")
      (node (ref "C42") (pin "2") (pinfunction "2_2") (pintype "passive"))
      (node (ref "C46") (pin "1") (pinfunction "1_1") (pintype "passive"))
      (node (ref "P1") (pin "4") (pinfunction "4_4") (pintype "passive"))
      (node (ref "P3") (pin "4") (pinfunction "4_4") (pintype "passive"))
      (node (ref "Q28") (pin "3") (pinfunction "D_3") (pintype "passive"))
      (node (ref "R39") (pin "2") (pinfunction "2_2") (pintype "passive"))
      (node (ref "R76") (pin "2") (pinfunction "2_2") (pintype "passive"))
      (node (ref "R96") (pin "1") (pinfunction "1_1") (pintype "passive"))
    )
    (net (code "17") (name "/V4CELL") (class "Default")
      (node (ref "C40") (pin "2") (pinfunction "2_2") (pintype "passive"))
      (node (ref "C42") (pin "1") (pinfunction "1_1") (pintype "passive"))
      (node (ref "P1") (pin "5") (pinfunction "5_5") (pintype "passive"))
      (node (ref "P3") (pin "5") (pinfunction "5_5") (pintype "passive"))
      (node (ref "Q25") (pin "3") (pinfunction "D_3") (pintype "passive"))
      (node (ref "R28") (pin "2") (pinfunction "2_2") (pintype "passive"))
      (node (ref "R54") (pin "1") (pinfunction "1_1") (pintype "passive"))
      (node (ref "R82") (pin "2") (pinfunction "2_2") (pintype "passive"))
    )
    (net (code "18") (name "/V5CELL") (class "Default")
      (node (ref "C39") (pin "2") (pinfunction "2_2") (pintype "passive"))
      (node (ref "C40") (pin "1") (pinfunction "1_1") (pintype "passive"))
      (node (ref "P1") (pin "6") (pinfunction "6_6") (pintype "passive"))
      (node (ref "P3") (pin "6") (pinfunction "6_6") (pintype "passive"))
      (node (ref "Q22") (pin "3") (pinfunction "D_3") (pintype "passive"))
      (node (ref "R19") (pin "2") (pinfunction "2_2") (pintype "passive"))
      (node (ref "R40") (pin "2") (pinfunction "2_2") (pintype "passive"))
      (node (ref "R55") (pin "1") (pinfunction "1_1") (pintype "passive"))
    )
    (net (code "19") (name "/V6CELL") (class "Default")
      (node (ref "C38") (pin "2") (pinfunction "2_2") (pintype "passive"))
      (node (ref "C39") (pin "1") (pinfunction "1_1") (pintype "passive"))
      (node (ref "P1") (pin "7") (pinfunction "7_7") (pintype "passive"))
      (node (ref "P3") (pin "7") (pinfunction "7_7") (pintype "passive"))
      (node (ref "Q14") (pin "3") (pinfunction "D_3") (pintype "passive"))
      (node (ref "R14") (pin "2") (pinfunction "2_2") (pintype "passive"))
      (node (ref "R31") (pin "1") (pinfunction "1_1") (pintype "passive"))
      (node (ref "R42") (pin "2") (pinfunction "2_2") (pintype "passive"))
    )
    (net (code "20") (name "/V7CELL") (class "Default")
      (node (ref "C36") (pin "2") (pinfunction "2_2") (pintype "passive"))
      (node (ref "C38") (pin "1") (pinfunction "1_1") (pintype "passive"))
      (node (ref "P1") (pin "8") (pinfunction "8_8") (pintype "passive"))
      (node (ref "P3") (pin "8") (pinfunction "8_8") (pintype "passive"))
      (node (ref "Q10") (pin "3") (pinfunction "D_3") (pintype "passive"))
      (node (ref "R23") (pin "2") (pinfunction "2_2") (pintype "passive"))
      (node (ref "R32") (pin "1") (pinfunction "1_1") (pintype "passive"))
      (node (ref "R8") (pin "2") (pinfunction "2_2") (pintype "passive"))
    )
    (net (code "21") (name "/V8CELL") (class "Default")
      (node (ref "C36") (pin "1") (pinfunction "1_1") (pintype "passive"))
      (node (ref "P1") (pin "9") (pinfunction "9_9") (pintype "passive"))
      (node (ref "P3") (pin "9") (pinfunction "9_9") (pintype "passive"))
      (node (ref "Q6") (pin "3") (pinfunction "D_3") (pintype "passive"))
      (node (ref "R1") (pin "2") (pinfunction "2_2") (pintype "passive"))
      (node (ref "R25") (pin "2") (pinfunction "2_2") (pintype "passive"))
    )
    (net (code "22") (name "5V") (class "Default")
      (node (ref "R4") (pin "2") (pinfunction "2_2") (pintype "passive"))
    )
    (net (code "23") (name "GND") (class "Default")
      (node (ref "C1") (pin "2") (pinfunction "2_2") (pintype "passive"))
      (node (ref "C10") (pin "1") (pinfunction "1_1") (pintype "passive"))
      (node (ref "C11") (pin "1") (pinfunction "1_1") (pintype "passive"))
      (node (ref "C12") (pin "1") (pinfunction "1_1") (pintype "passive"))
      (node (ref "C13") (pin "1") (pinfunction "1_1") (pintype "passive"))
      (node (ref "C2") (pin "2") (pinfunction "2_2") (pintype "passive"))
      (node (ref "C3") (pin "2") (pinfunction "2_2") (pintype "passive"))
      (node (ref "C4") (pin "2") (pinfunction "2_2") (pintype "passive"))
      (node (ref "C6") (pin "1") (pinfunction "1_1") (pintype "passive"))
      (node (ref "C7") (pin "1") (pinfunction "1_1") (pintype "passive"))
      (node (ref "C8") (pin "1") (pinfunction "1_1") (pintype "passive"))
      (node (ref "C9") (pin "1") (pinfunction "1_1") (pintype "passive"))
      (node (ref "Q11") (pin "2") (pinfunction "D_2") (pintype "passive"))
      (node (ref "Q15") (pin "2") (pinfunction "D_2") (pintype "passive"))
      (node (ref "Q23") (pin "2") (pinfunction "D_2") (pintype "passive"))
      (node (ref "Q26") (pin "2") (pinfunction "D_2") (pintype "passive"))
      (node (ref "Q29") (pin "2") (pinfunction "D_2") (pintype "passive"))
      (node (ref "Q3") (pin "2") (pinfunction "D_2") (pintype "passive"))
      (node (ref "Q32") (pin "2") (pinfunction "D_2") (pintype "passive"))
      (node (ref "Q36") (pin "2") (pinfunction "D_2") (pintype "passive"))
      (node (ref "Q37") (pin "1") (pinfunction "S_1") (pintype "passive"))
      (node (ref "Q37") (pin "2") (pinfunction "S_2") (pintype "passive"))
      (node (ref "Q37") (pin "3") (pinfunction "S_3") (pintype "passive"))
      (node (ref "Q53") (pin "2") (pinfunction "D_2") (pintype "passive"))
      (node (ref "Q7") (pin "2") (pinfunction "D_2") (pintype "passive"))
      (node (ref "Q8") (pin "2") (pinfunction "D_2") (pintype "passive"))
      (node (ref "R106") (pin "1") (pinfunction "1_1") (pintype "passive"))
      (node (ref "R109") (pin "1") (pinfunction "1_1") (pintype "passive"))
      (node (ref "R111") (pin "1") (pinfunction "1_1") (pintype "passive"))
      (node (ref "R12") (pin "2") (pinfunction "2_2") (pintype "passive"))
      (node (ref "R123") (pin "2") (pinfunction "2_2") (pintype "passive"))
      (node (ref "R124") (pin "1") (pinfunction "1_1") (pintype "passive"))
      (node (ref "R211") (pin "2") (pinfunction "2_2") (pintype "passive"))
      (node (ref "R24") (pin "1") (pinfunction "1_1") (pintype "passive"))
      (node (ref "R26") (pin "1") (pinfunction "1_1") (pintype "passive"))
      (node (ref "R41") (pin "1") (pinfunction "1_1") (pintype "passive"))
      (node (ref "R44") (pin "1") (pinfunction "1_1") (pintype "passive"))
      (node (ref "R77") (pin "1") (pinfunction "1_1") (pintype "passive"))
      (node (ref "R84") (pin "1") (pinfunction "1_1") (pintype "passive"))
      (node (ref "U1") (pin "4") (pinfunction "4_4") (pintype "passive"))
      (node (ref "U2") (pin "4") (pinfunction "4_4") (pintype "passive"))
      (node (ref "U3") (pin "4") (pinfunction "4_4") (pintype "passive"))
      (node (ref "U4") (pin "4") (pinfunction "4_4") (pintype "passive"))
    )
    (net (code "24") (name "Net-(D4-A)") (class "Default")
      (node (ref "D4") (pin "1") (pinfunction "A_1") (pintype "passive"))
      (node (ref "R11") (pin "1") (pinfunction "1_1") (pintype "passive"))
    )
    (net (code "25") (name "Net-(D6-A)") (class "Default")
      (node (ref "D6") (pin "1") (pinfunction "A_1") (pintype "passive"))
      (node (ref "R17") (pin "1") (pinfunction "1_1") (pintype "passive"))
    )
    (net (code "26") (name "Net-(D8-A)") (class "Default")
      (node (ref "D8") (pin "1") (pinfunction "A_1") (pintype "passive"))
      (node (ref "R22") (pin "1") (pinfunction "1_1") (pintype "passive"))
    )
    (net (code "27") (name "Net-(D10-A)") (class "Default")
      (node (ref "D10") (pin "1") (pinfunction "A_1") (pintype "passive"))
      (node (ref "R35") (pin "1") (pinfunction "1_1") (pintype "passive"))
    )
    (net (code "28") (name "Net-(D10-K)") (class "Default")
      (node (ref "D10") (pin "2") (pinfunction "K_2") (pintype "passive"))
      (node (ref "D16") (pin "2") (pinfunction "K_2") (pintype "passive"))
      (node (ref "D21") (pin "2") (pinfunction "K_2") (pintype "passive"))
      (node (ref "D23") (pin "2") (pinfunction "K_2") (pintype "passive"))
      (node (ref "D25") (pin "2") (pinfunction "K_2") (pintype "passive"))
      (node (ref "D4") (pin "2") (pinfunction "K_2") (pintype "passive"))
      (node (ref "D6") (pin "2") (pinfunction "K_2") (pintype "passive"))
      (node (ref "D8") (pin "2") (pinfunction "K_2") (pintype "passive"))
      (node (ref "Q36") (pin "3") (pinfunction "S_3") (pintype "passive"))
    )
    (net (code "29") (name "Net-(D16-A)") (class "Default")
      (node (ref "D16") (pin "1") (pinfunction "A_1") (pintype "passive"))
      (node (ref "R49") (pin "1") (pinfunction "1_1") (pintype "passive"))
    )
    (net (code "30") (name "Net-(D21-A)") (class "Default")
      (node (ref "D21") (pin "1") (pinfunction "A_1") (pintype "passive"))
      (node (ref "R69") (pin "1") (pinfunction "1_1") (pintype "passive"))
    )
    (net (code "31") (name "Net-(D23-A)") (class "Default")
      (node (ref "D23") (pin "1") (pinfunction "A_1") (pintype "passive"))
      (node (ref "R103") (pin "1") (pinfunction "1_1") (pintype "passive"))
    )
    (net (code "32") (name "Net-(D25-A)") (class "Default")
      (node (ref "D25") (pin "1") (pinfunction "A_1") (pintype "passive"))
      (node (ref "R114") (pin "1") (pinfunction "1_1") (pintype "passive"))
    )
    (net (code "33") (name "Net-(Q1-G)") (class "Default")
      (node (ref "Q1") (pin "4") (pinfunction "G_4") (pintype "passive"))
      (node (ref "Q2") (pin "4") (pinfunction "G_4") (pintype "passive"))
      (node (ref "R2") (pin "1") (pinfunction "1_1") (pintype "passive"))
      (node (ref "R6") (pin "2") (pinfunction "2_2") (pintype "passive"))
    )
    (net (code "34") (name "Net-(Q1-S-Pad1)") (class "Default")
      (node (ref "Q1") (pin "1") (pinfunction "S_1") (pintype "passive"))
      (node (ref "Q1") (pin "2") (pinfunction "S_2") (pintype "passive"))
      (node (ref "Q1") (pin "3") (pinfunction "S_3") (pintype "passive"))
      (node (ref "Q2") (pin "1") (pinfunction "S_1") (pintype "passive"))
      (node (ref "Q2") (pin "2") (pinfunction "S_2") (pintype "passive"))
      (node (ref "Q2") (pin "3") (pinfunction "S_3") (pintype "passive"))
      (node (ref "R2") (pin "2") (pinfunction "2_2") (pintype "passive"))
    )
    (net (code "35") (name "Net-(Q3-S)") (class "Default")
      (node (ref "Q3") (pin "3") (pinfunction "S_3") (pintype "passive"))
      (node (ref "R1") (pin "1") (pinfunction "1_1") (pintype "passive"))
    )
    (net (code "36") (name "Net-(Q6-G)") (class "Default")
      (node (ref "Q6") (pin "1") (pinfunction "G_1") (pintype "passive"))
      (node (ref "Q9") (pin "1") (pinfunction "G_1") (pintype "passive"))
      (node (ref "R10") (pin "2") (pinfunction "2_2") (pintype "passive"))
      (node (ref "R11") (pin "2") (pinfunction "2_2") (pintype "passive"))
    )
    (net (code "37") (name "Net-(Q6-S)") (class "Default")
      (node (ref "Q6") (pin "2") (pinfunction "S_2") (pintype "passive"))
      (node (ref "Q9") (pin "2") (pinfunction "S_2") (pintype "passive"))
      (node (ref "R10") (pin "1") (pinfunction "1_1") (pintype "passive"))
    )
    (net (code "38") (name "Net-(Q7-S)") (class "Default")
      (node (ref "Q7") (pin "3") (pinfunction "S_3") (pintype "passive"))
      (node (ref "R6") (pin "1") (pinfunction "1_1") (pintype "passive"))
    )
    (net (code "39") (name "Net-(Q8-S)") (class "Default")
      (node (ref "Q8") (pin "3") (pinfunction "S_3") (pintype "passive"))
      (node (ref "R8") (pin "1") (pinfunction "1_1") (pintype "passive"))
    )
    (net (code "40") (name "Net-(Q9-D)") (class "Default")
      (node (ref "D3") (pin "1") (pinfunction "1_1") (pintype "passive"))
      (node (ref "Q2") (pin "5") (pinfunction "D_5") (pintype "passive"))
      (node (ref "Q2") (pin "6") (pinfunction "D_6") (pintype "passive"))
      (node (ref "Q2") (pin "7") (pinfunction "D_7") (pintype "passive"))
      (node (ref "Q2") (pin "8") (pinfunction "D_8") (pintype "passive"))
      (node (ref "Q9") (pin "3") (pinfunction "D_3") (pintype "passive"))
      (node (ref "R9") (pin "2") (pinfunction "2_2") (pintype "passive"))
    )
    (net (code "41") (name "Net-(Q10-G)") (class "Default")
      (node (ref "Q10") (pin "1") (pinfunction "G_1") (pintype "passive"))
      (node (ref "Q13") (pin "1") (pinfunction "G_1") (pintype "passive"))
      (node (ref "R16") (pin "2") (pinfunction "2_2") (pintype "passive"))
      (node (ref "R17") (pin "2") (pinfunction "2_2") (pintype "passive"))
    )
    (net (code "42") (name "Net-(Q10-S)") (class "Default")
      (node (ref "Q10") (pin "2") (pinfunction "S_2") (pintype "passive"))
      (node (ref "Q13") (pin "2") (pinfunction "S_2") (pintype "passive"))
      (node (ref "R16") (pin "1") (pinfunction "1_1") (pintype "passive"))
    )
    (net (code "43") (name "Net-(Q11-S)") (class "Default")
      (node (ref "Q11") (pin "3") (pinfunction "S_3") (pintype "passive"))
      (node (ref "R14") (pin "1") (pinfunction "1_1") (pintype "passive"))
    )
    (net (code "44") (name "Net-(Q13-D)") (class "Default")
      (node (ref "D3") (pin "2") (pinfunction "2_2") (pintype "passive"))
      (node (ref "D5") (pin "1") (pinfunction "1_1") (pintype "passive"))
      (node (ref "Q13") (pin "3") (pinfunction "D_3") (pintype "passive"))
      (node (ref "R15") (pin "2") (pinfunction "2_2") (pintype "passive"))
      (node (ref "R9") (pin "1") (pinfunction "1_1") (pintype "passive"))
    )
    (net (code "45") (name "Net-(Q14-G)") (class "Default")
      (node (ref "Q14") (pin "1") (pinfunction "G_1") (pintype "passive"))
      (node (ref "Q16") (pin "1") (pinfunction "G_1") (pintype "passive"))
      (node (ref "R21") (pin "2") (pinfunction "2_2") (pintype "passive"))
      (node (ref "R22") (pin "2") (pinfunction "2_2") (pintype "passive"))
    )
    (net (code "46") (name "Net-(Q14-S)") (class "Default")
      (node (ref "Q14") (pin "2") (pinfunction "S_2") (pintype "passive"))
      (node (ref "Q16") (pin "2") (pinfunction "S_2") (pintype "passive"))
      (node (ref "R21") (pin "1") (pinfunction "1_1") (pintype "passive"))
    )
    (net (code "47") (name "Net-(Q15-S)") (class "Default")
      (node (ref "Q15") (pin "3") (pinfunction "S_3") (pintype "passive"))
      (node (ref "R19") (pin "1") (pinfunction "1_1") (pintype "passive"))
    )
    (net (code "48") (name "Net-(Q16-D)") (class "Default")
      (node (ref "D5") (pin "2") (pinfunction "2_2") (pintype "passive"))
      (node (ref "D7") (pin "1") (pinfunction "1_1") (pintype "passive"))
      (node (ref "Q16") (pin "3") (pinfunction "D_3") (pintype "passive"))
      (node (ref "R15") (pin "1") (pinfunction "1_1") (pintype "passive"))
      (node (ref "R20") (pin "2") (pinfunction "2_2") (pintype "passive"))
    )
    (net (code "49") (name "Net-(Q20-G)") (class "Default")
      (node (ref "Q20") (pin "1") (pinfunction "G_1") (pintype "passive"))
      (node (ref "Q38") (pin "1") (pinfunction "G_1") (pintype "passive"))
      (node (ref "R208") (pin "1") (pinfunction "1_1") (pintype "passive"))
      (node (ref "R209") (pin "2") (pinfunction "2_2") (pintype "passive"))
    )
    (net (code "50") (name "Net-(Q20-S)") (class "Default")
      (node (ref "Q20") (pin "2") (pinfunction "S_2") (pintype "passive"))
      (node (ref "Q38") (pin "2") (pinfunction "S_2") (pintype "passive"))
      (node (ref "R208") (pin "2") (pinfunction "2_2") (pintype "passive"))
    )
    (net (code "51") (name "Net-(Q22-G)") (class "Default")
      (node (ref "Q22") (pin "1") (pinfunction "G_1") (pintype "passive"))
      (node (ref "Q24") (pin "1") (pinfunction "G_1") (pintype "passive"))
      (node (ref "R34") (pin "2") (pinfunction "2_2") (pintype "passive"))
      (node (ref "R35") (pin "2") (pinfunction "2_2") (pintype "passive"))
    )
    (net (code "52") (name "Net-(Q22-S)") (class "Default")
      (node (ref "Q22") (pin "2") (pinfunction "S_2") (pintype "passive"))
      (node (ref "Q24") (pin "2") (pinfunction "S_2") (pintype "passive"))
      (node (ref "R34") (pin "1") (pinfunction "1_1") (pintype "passive"))
    )
    (net (code "53") (name "Net-(Q23-S)") (class "Default")
      (node (ref "Q23") (pin "3") (pinfunction "S_3") (pintype "passive"))
      (node (ref "R28") (pin "1") (pinfunction "1_1") (pintype "passive"))
    )
    (net (code "54") (name "Net-(Q24-D)") (class "Default")
      (node (ref "D7") (pin "2") (pinfunction "2_2") (pintype "passive"))
      (node (ref "D9") (pin "1") (pinfunction "1_1") (pintype "passive"))
      (node (ref "Q24") (pin "3") (pinfunction "D_3") (pintype "passive"))
      (node (ref "R20") (pin "1") (pinfunction "1_1") (pintype "passive"))
      (node (ref "R33") (pin "2") (pinfunction "2_2") (pintype "passive"))
    )
    (net (code "55") (name "Net-(Q25-G)") (class "Default")
      (node (ref "Q25") (pin "1") (pinfunction "G_1") (pintype "passive"))
      (node (ref "Q27") (pin "1") (pinfunction "G_1") (pintype "passive"))
      (node (ref "R46") (pin "2") (pinfunction "2_2") (pintype "passive"))
      (node (ref "R49") (pin "2") (pinfunction "2_2") (pintype "passive"))
    )
    (net (code "56") (name "Net-(Q25-S)") (class "Default")
      (node (ref "Q25") (pin "2") (pinfunction "S_2") (pintype "passive"))
      (node (ref "Q27") (pin "2") (pinfunction "S_2") (pintype "passive"))
      (node (ref "R46") (pin "1") (pinfunction "1_1") (pintype "passive"))
    )
    (net (code "57") (name "Net-(Q26-S)") (class "Default")
      (node (ref "Q26") (pin "3") (pinfunction "S_3") (pintype "passive"))
      (node (ref "R39") (pin "1") (pinfunction "1_1") (pintype "passive"))
    )
    (net (code "58") (name "Net-(Q27-D)") (class "Default")
      (node (ref "D11") (pin "1") (pinfunction "1_1") (pintype "passive"))
      (node (ref "D9") (pin "2") (pinfunction "2_2") (pintype "passive"))
      (node (ref "Q27") (pin "3") (pinfunction "D_3") (pintype "passive"))
      (node (ref "R33") (pin "1") (pinfunction "1_1") (pintype "passive"))
      (node (ref "R45") (pin "2") (pinfunction "2_2") (pintype "passive"))
    )
    (net (code "59") (name "Net-(Q28-G)") (class "Default")
      (node (ref "Q28") (pin "1") (pinfunction "G_1") (pintype "passive"))
      (node (ref "Q30") (pin "1") (pinfunction "G_1") (pintype "passive"))
      (node (ref "R61") (pin "2") (pinfunction "2_2") (pintype "passive"))
      (node (ref "R69") (pin "2") (pinfunction "2_2") (pintype "passive"))
    )
    (net (code "60") (name "Net-(Q28-S)") (class "Default")
      (node (ref "Q28") (pin "2") (pinfunction "S_2") (pintype "passive"))
      (node (ref "Q30") (pin "2") (pinfunction "S_2") (pintype "passive"))
      (node (ref "R61") (pin "1") (pinfunction "1_1") (pintype "passive"))
    )
    (net (code "61") (name "Net-(Q29-S)") (class "Default")
      (node (ref "Q29") (pin "3") (pinfunction "S_3") (pintype "passive"))
      (node (ref "R57") (pin "1") (pinfunction "1_1") (pintype "passive"))
    )
    (net (code "62") (name "Net-(Q30-D)") (class "Default")
      (node (ref "D11") (pin "2") (pinfunction "2_2") (pintype "passive"))
      (node (ref "D19") (pin "1") (pinfunction "1_1") (pintype "passive"))
      (node (ref "Q30") (pin "3") (pinfunction "D_3") (pintype "passive"))
      (node (ref "R45") (pin "1") (pinfunction "1_1") (pintype "passive"))
      (node (ref "R60") (pin "2") (pinfunction "2_2") (pintype "passive"))
    )
    (net (code "63") (name "Net-(Q31-G)") (class "Default")
      (node (ref "Q31") (pin "1") (pinfunction "G_1") (pintype "passive"))
      (node (ref "Q33") (pin "1") (pinfunction "G_1") (pintype "passive"))
      (node (ref "R102") (pin "2") (pinfunction "2_2") (pintype "passive"))
      (node (ref "R103") (pin "2") (pinfunction "2_2") (pintype "passive"))
    )
    (net (code "64") (name "Net-(Q31-S)") (class "Default")
      (node (ref "Q31") (pin "2") (pinfunction "S_2") (pintype "passive"))
      (node (ref "Q33") (pin "2") (pinfunction "S_2") (pintype "passive"))
      (node (ref "R102") (pin "1") (pinfunction "1_1") (pintype "passive"))
    )
    (net (code "65") (name "Net-(Q32-S)") (class "Default")
      (node (ref "Q32") (pin "3") (pinfunction "S_3") (pintype "passive"))
      (node (ref "R92") (pin "1") (pinfunction "1_1") (pintype "passive"))
    )
    (net (code "66") (name "Net-(Q33-D)") (class "Default")
      (node (ref "D19") (pin "2") (pinfunction "2_2") (pintype "passive"))
      (node (ref "D22") (pin "1") (pinfunction "1_1") (pintype "passive"))
      (node (ref "Q33") (pin "3") (pinfunction "D_3") (pintype "passive"))
      (node (ref "R101") (pin "2") (pinfunction "2_2") (pintype "passive"))
      (node (ref "R60") (pin "1") (pinfunction "1_1") (pintype "passive"))
    )
    (net (code "67") (name "Net-(Q34-G)") (class "Default")
      (node (ref "Q34") (pin "1") (pinfunction "G_1") (pintype "passive"))
      (node (ref "Q35") (pin "1") (pinfunction "G_1") (pintype "passive"))
      (node (ref "R113") (pin "2") (pinfunction "2_2") (pintype "passive"))
      (node (ref "R114") (pin "2") (pinfunction "2_2") (pintype "passive"))
    )
    (net (code "68") (name "Net-(Q34-S)") (class "Default")
      (node (ref "Q34") (pin "2") (pinfunction "S_2") (pintype "passive"))
      (node (ref "Q35") (pin "2") (pinfunction "S_2") (pintype "passive"))
      (node (ref "R113") (pin "1") (pinfunction "1_1") (pintype "passive"))
    )
    (net (code "69") (name "Net-(Q35-D)") (class "Default")
      (node (ref "D22") (pin "2") (pinfunction "2_2") (pintype "passive"))
      (node (ref "D24") (pin "1") (pinfunction "1_1") (pintype "passive"))
      (node (ref "Q35") (pin "3") (pinfunction "D_3") (pintype "passive"))
      (node (ref "R101") (pin "1") (pinfunction "1_1") (pintype "passive"))
      (node (ref "R112") (pin "2") (pinfunction "2_2") (pintype "passive"))
    )
    (net (code "70") (name "Net-(Q38-D)") (class "Default")
      (node (ref "Q38") (pin "3") (pinfunction "D_3") (pintype "passive"))
      (node (ref "R4") (pin "1") (pinfunction "1_1") (pintype "passive"))
    )
    (net (code "71") (name "Net-(Q53-S)") (class "Default")
      (node (ref "Q53") (pin "3") (pinfunction "S_3") (pintype "passive"))
      (node (ref "R209") (pin "1") (pinfunction "1_1") (pintype "passive"))
    )
    (net (code "72") (name "Net-(R23-Pad1)") (class "Default")
      (node (ref "R23") (pin "1") (pinfunction "1_1") (pintype "passive"))
      (node (ref "R24") (pin "2") (pinfunction "2_2") (pintype "passive"))
      (node (ref "U1") (pin "5") (pinfunction "5_5") (pintype "passive"))
    )
    (net (code "73") (name "Net-(R25-Pad1)") (class "Default")
      (node (ref "R25") (pin "1") (pinfunction "1_1") (pintype "passive"))
      (node (ref "R26") (pin "2") (pinfunction "2_2") (pintype "passive"))
      (node (ref "U1") (pin "3") (pinfunction "3_3") (pintype "passive"))
    )
    (net (code "74") (name "Net-(R29-Pad2)") (class "Default")
      (node (ref "R29") (pin "2") (pinfunction "2_2") (pintype "passive"))
      (node (ref "R36") (pin "2") (pinfunction "2_2") (pintype "passive"))
      (node (ref "U1") (pin "7") (pinfunction "7_7") (pintype "passive"))
    )
    (net (code "75") (name "Net-(R30-Pad2)") (class "Default")
      (node (ref "R30") (pin "2") (pinfunction "2_2") (pintype "passive"))
      (node (ref "R37") (pin "2") (pinfunction "2_2") (pintype "passive"))
      (node (ref "U1") (pin "1") (pinfunction "1_1") (pintype "passive"))
    )
    (net (code "76") (name "Net-(R31-Pad2)") (class "Default")
      (node (ref "R31") (pin "2") (pinfunction "2_2") (pintype "passive"))
      (node (ref "R36") (pin "1") (pinfunction "1_1") (pintype "passive"))
      (node (ref "U1") (pin "6") (pinfunction "6_6") (pintype "passive"))
    )
    (net (code "77") (name "Net-(R32-Pad2)") (class "Default")
      (node (ref "R32") (pin "2") (pinfunction "2_2") (pintype "passive"))
      (node (ref "R37") (pin "1") (pinfunction "1_1") (pintype "passive"))
      (node (ref "U1") (pin "2") (pinfunction "2_2") (pintype "passive"))
    )
    (net (code "78") (name "Net-(R40-Pad1)") (class "Default")
      (node (ref "R40") (pin "1") (pinfunction "1_1") (pintype "passive"))
      (node (ref "R41") (pin "2") (pinfunction "2_2") (pintype "passive"))
      (node (ref "U2") (pin "5") (pinfunction "5_5") (pintype "passive"))
    )
    (net (code "79") (name "Net-(R42-Pad1)") (class "Default")
      (node (ref "R42") (pin "1") (pinfunction "1_1") (pintype "passive"))
      (node (ref "R44") (pin "2") (pinfunction "2_2") (pintype "passive"))
      (node (ref "U2") (pin "3") (pinfunction "3_3") (pintype "passive"))
    )
    (net (code "80") (name "Net-(R50-Pad2)") (class "Default")
      (node (ref "R50") (pin "2") (pinfunction "2_2") (pintype "passive"))
      (node (ref "R58") (pin "2") (pinfunction "2_2") (pintype "passive"))
      (node (ref "U2") (pin "7") (pinfunction "7_7") (pintype "passive"))
    )
    (net (code "81") (name "Net-(R53-Pad2)") (class "Default")
      (node (ref "R53") (pin "2") (pinfunction "2_2") (pintype "passive"))
      (node (ref "R59") (pin "2") (pinfunction "2_2") (pintype "passive"))
      (node (ref "U2") (pin "1") (pinfunction "1_1") (pintype "passive"))
    )
    (net (code "82") (name "Net-(R54-Pad2)") (class "Default")
      (node (ref "R54") (pin "2") (pinfunction "2_2") (pintype "passive"))
      (node (ref "R58") (pin "1") (pinfunction "1_1") (pintype "passive"))
      (node (ref "U2") (pin "6") (pinfunction "6_6") (pintype "passive"))
    )
    (net (code "83") (name "Net-(R55-Pad2)") (class "Default")
      (node (ref "R55") (pin "2") (pinfunction "2_2") (pintype "passive"))
      (node (ref "R59") (pin "1") (pinfunction "1_1") (pintype "passive"))
      (node (ref "U2") (pin "2") (pinfunction "2_2") (pintype "passive"))
    )
    (net (code "84") (name "Net-(R76-Pad1)") (class "Default")
      (node (ref "R76") (pin "1") (pinfunction "1_1") (pintype "passive"))
      (node (ref "R77") (pin "2") (pinfunction "2_2") (pintype "passive"))
      (node (ref "U3") (pin "5") (pinfunction "5_5") (pintype "passive"))
    )
    (net (code "85") (name "Net-(R82-Pad1)") (class "Default")
      (node (ref "R82") (pin "1") (pinfunction "1_1") (pintype "passive"))
      (node (ref "R84") (pin "2") (pinfunction "2_2") (pintype "passive"))
      (node (ref "U3") (pin "3") (pinfunction "3_3") (pintype "passive"))
    )
    (net (code "86") (name "Net-(R104-Pad1)") (class "Default")
      (node (ref "R104") (pin "1") (pinfunction "1_1") (pintype "passive"))
      (node (ref "R95") (pin "2") (pinfunction "2_2") (pintype "passive"))
      (node (ref "U3") (pin "6") (pinfunction "6_6") (pintype "passive"))
    )
    (net (code "87") (name "Net-(R104-Pad2)") (class "Default")
      (node (ref "R104") (pin "2") (pinfunction "2_2") (pintype "passive"))
      (node (ref "R93") (pin "2") (pinfunction "2_2") (pintype "passive"))
      (node (ref "U3") (pin "7") (pinfunction "7_7") (pintype "passive"))
    )
    (net (code "88") (name "Net-(R105-Pad1)") (class "Default")
      (node (ref "R105") (pin "1") (pinfunction "1_1") (pintype "passive"))
      (node (ref "R96") (pin "2") (pinfunction "2_2") (pintype "passive"))
      (node (ref "U3") (pin "2") (pinfunction "2_2") (pintype "passive"))
    )
    (net (code "89") (name "Net-(R105-Pad2)") (class "Default")
      (node (ref "R105") (pin "2") (pinfunction "2_2") (pintype "passive"))
      (node (ref "R94") (pin "2") (pinfunction "2_2") (pintype "passive"))
      (node (ref "U3") (pin "1") (pinfunction "1_1") (pintype "passive"))
    )
    (net (code "90") (name "Net-(R108-Pad1)") (class "Default")
      (node (ref "R108") (pin "1") (pinfunction "1_1") (pintype "passive"))
      (node (ref "R109") (pin "2") (pinfunction "2_2") (pintype "passive"))
      (node (ref "U4") (pin "5") (pinfunction "5_5") (pintype "passive"))
    )
    (net (code "91") (name "Net-(R110-Pad1)") (class "Default")
      (node (ref "R110") (pin "1") (pinfunction "1_1") (pintype "passive"))
      (node (ref "R111") (pin "2") (pinfunction "2_2") (pintype "passive"))
      (node (ref "U4") (pin "3") (pinfunction "3_3") (pintype "passive"))
    )
    (net (code "92") (name "Net-(R115-Pad2)") (class "Default")
      (node (ref "R115") (pin "2") (pinfunction "2_2") (pintype "passive"))
      (node (ref "R121") (pin "2") (pinfunction "2_2") (pintype "passive"))
      (node (ref "U4") (pin "7") (pinfunction "7_7") (pintype "passive"))
    )
    (net (code "93") (name "Net-(R116-Pad2)") (class "Default")
      (node (ref "R116") (pin "2") (pinfunction "2_2") (pintype "passive"))
      (node (ref "R122") (pin "2") (pinfunction "2_2") (pintype "passive"))
      (node (ref "U4") (pin "1") (pinfunction "1_1") (pintype "passive"))
    )
    (net (code "94") (name "Net-(R117-Pad2)") (class "Default")
      (node (ref "R117") (pin "2") (pinfunction "2_2") (pintype "passive"))
      (node (ref "R121") (pin "1") (pinfunction "1_1") (pintype "passive"))
      (node (ref "U4") (pin "6") (pinfunction "6_6") (pintype "passive"))
    )
    (net (code "95") (name "Net-(R118-Pad2)") (class "Default")
      (node (ref "R118") (pin "2") (pinfunction "2_2") (pintype "passive"))
      (node (ref "R122") (pin "1") (pinfunction "1_1") (pintype "passive"))
      (node (ref "U4") (pin "2") (pinfunction "2_2") (pintype "passive"))
    )
    (net (code "96") (name "VIN") (class "Default")
      (node (ref "C1") (pin "1") (pinfunction "1_1") (pintype "passive"))
      (node (ref "C2") (pin "1") (pinfunction "1_1") (pintype "passive"))
      (node (ref "C3") (pin "1") (pinfunction "1_1") (pintype "passive"))
      (node (ref "C4") (pin "1") (pinfunction "1_1") (pintype "passive"))
      (node (ref "U1") (pin "8") (pinfunction "8_8") (pintype "passive"))
      (node (ref "U2") (pin "8") (pinfunction "8_8") (pintype "passive"))
      (node (ref "U3") (pin "8") (pinfunction "8_8") (pintype "passive"))
      (node (ref "U4") (pin "8") (pinfunction "8_8") (pintype "passive"))
    )
  )
)
